# Quadcopter.net
KiCad netlist of a schematic drawn in Altium Designer
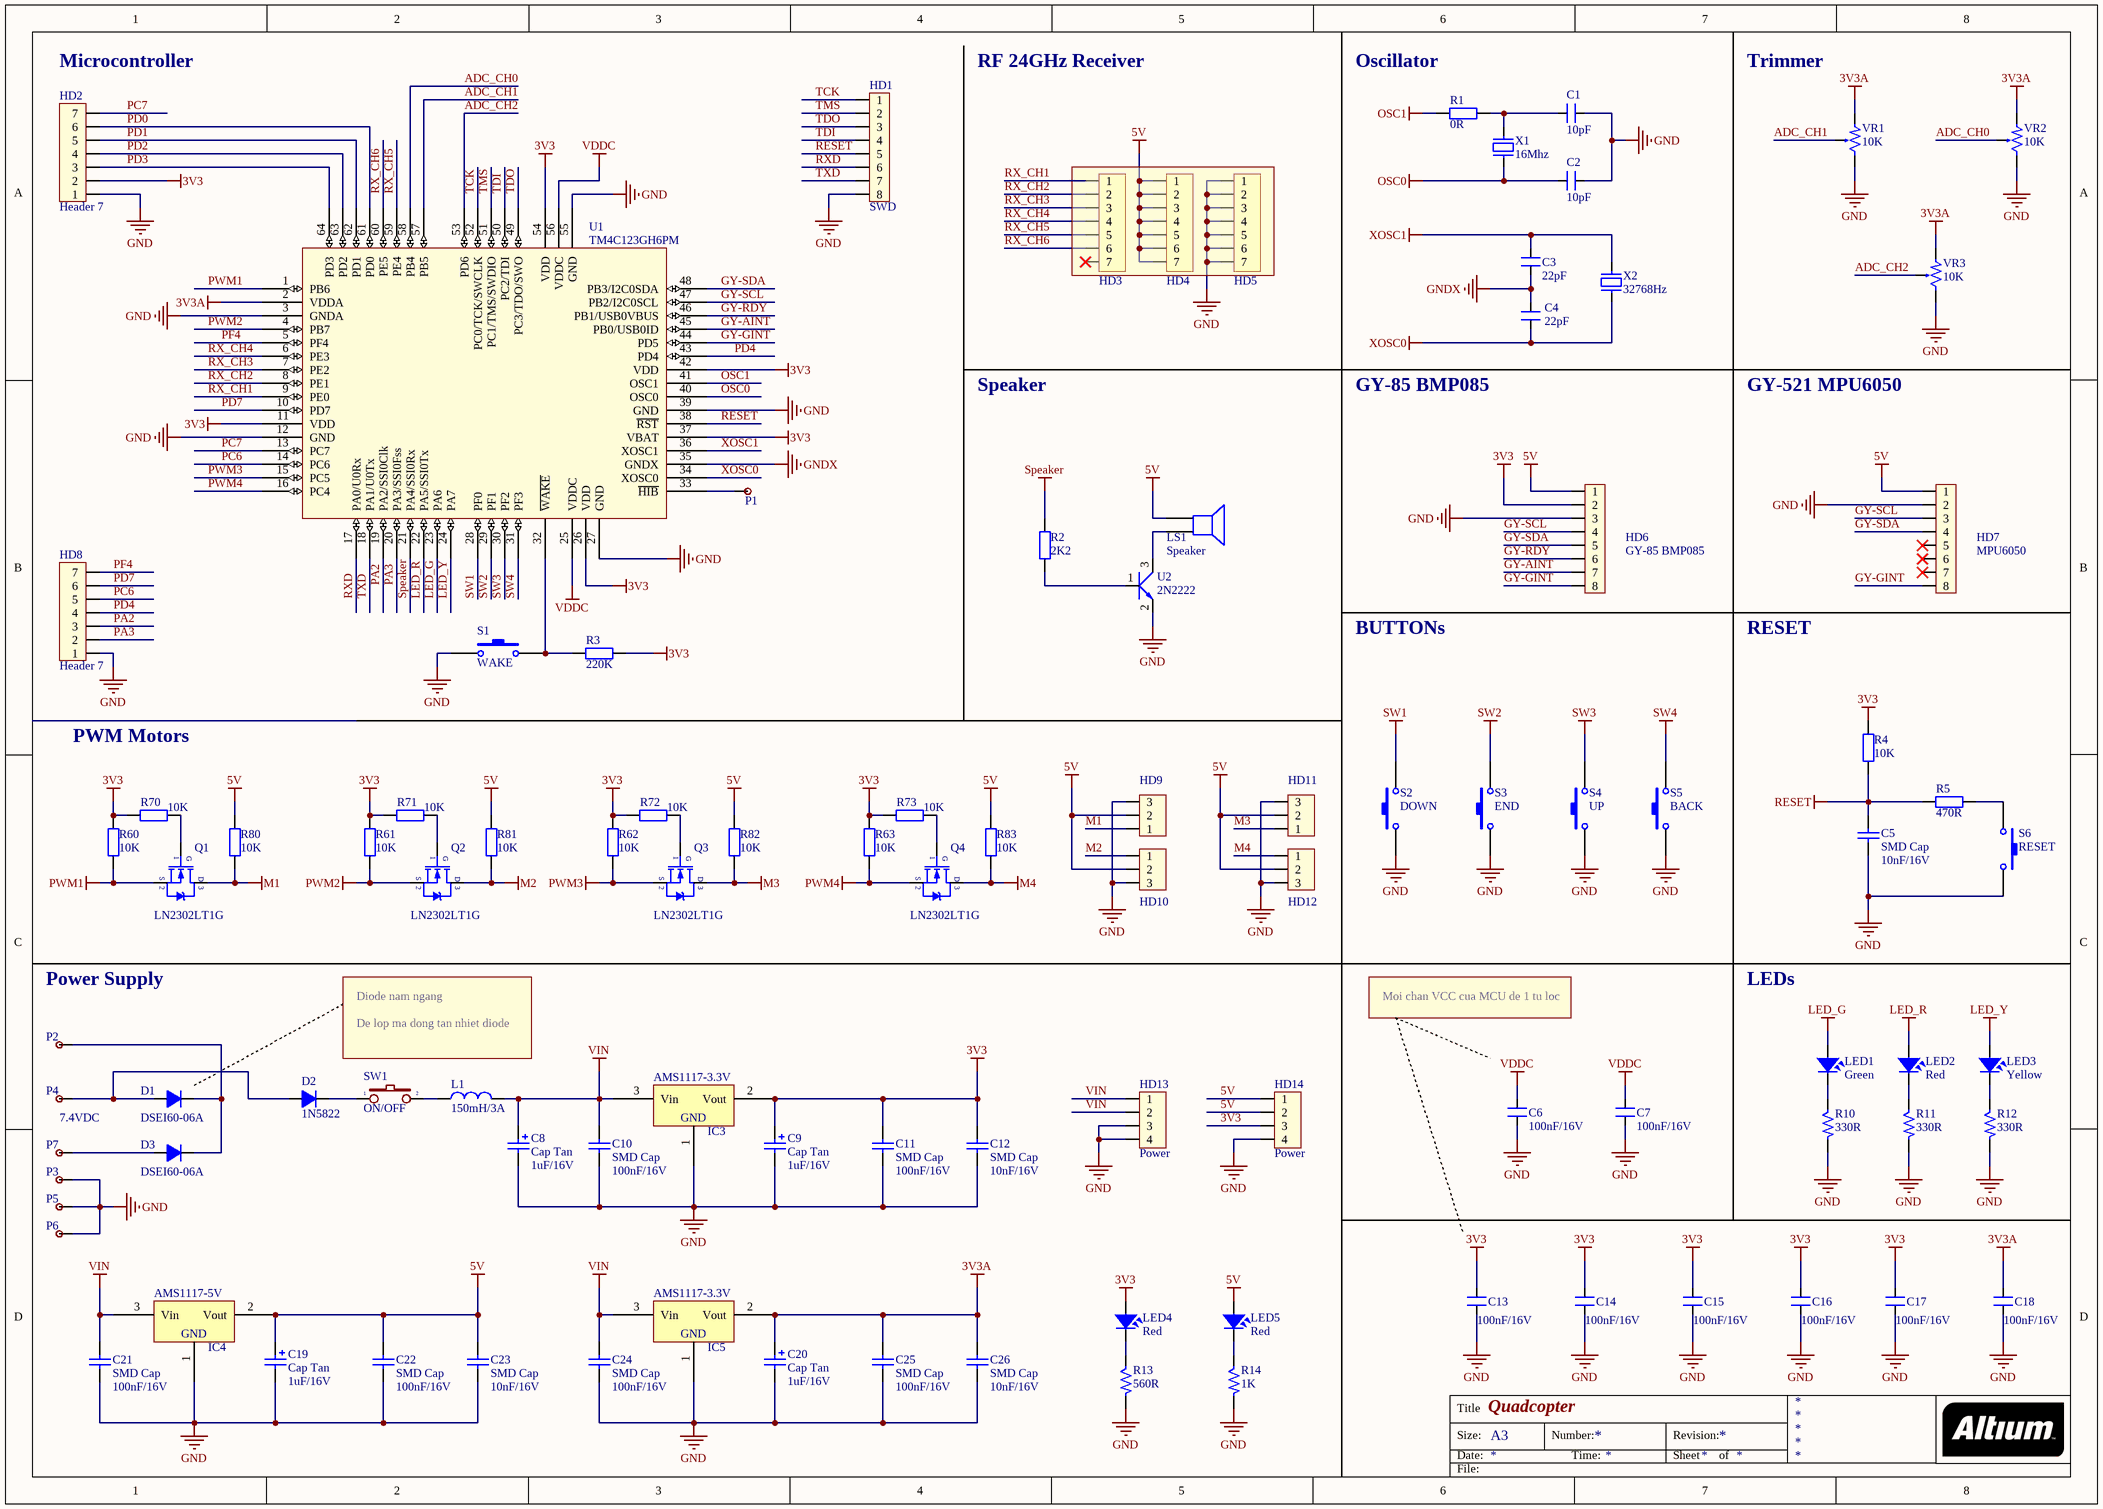
[diagram p0: Quadcopter.schdoc]

(export (version "E")
  (design (tool "Eeschema 10.0.6"))
  (components
    (comp (ref "C1")
      (value "10pF")
      (footprint "C0603")
      (description "0805-SMD Capacitor")
      (libsource (lib "syhaunguyen") (part "CN1"))
    )
    (comp (ref "C2")
      (value "10pF")
      (footprint "C0603")
      (description "0805-SMD Capacitor")
      (libsource (lib "syhaunguyen") (part "CN1"))
    )
    (comp (ref "C3")
      (value "22pF")
      (footprint "C0603")
      (description "0805-SMD Capacitor")
      (libsource (lib "syhaunguyen") (part "CN1"))
    )
    (comp (ref "C4")
      (value "22pF")
      (footprint "C0603")
      (description "0805-SMD Capacitor")
      (libsource (lib "syhaunguyen") (part "CN1"))
    )
    (comp (ref "C5")
      (value "SMD Cap")
      (footprint "C0603")
      (description "0805-10nF-50V Cap")
      (fields (field (name "ALTIUM_VALUE") "10nF/16V"))
      (libsource (lib "Miscellaneous Devices") (part "Cap"))
    )
    (comp (ref "C6")
      (value "100nF/16V")
      (footprint "C0603")
      (description "0805-SMD Capacitor")
      (fields (field (name "Comment") "SMD Cap"))
      (libsource (lib "syhaunguyen") (part "CN1"))
    )
    (comp (ref "C7")
      (value "100nF/16V")
      (footprint "C0603")
      (description "0805-SMD Capacitor")
      (fields (field (name "Comment") "SMD Cap"))
      (libsource (lib "syhaunguyen") (part "CN1"))
    )
    (comp (ref "C8")
      (value "Cap Tan")
      (footprint "CAP_TANTA_1uF_16V")
      (description "Cap Tantalum")
      (fields (field (name "ALTIUM_VALUE") "1uF/16V"))
      (libsource (lib "PassiveComponents_Sau") (part "Cap Pol2"))
    )
    (comp (ref "C9")
      (value "Cap Tan")
      (footprint "CAP_TANTA_1uF_16V")
      (description "Cap Tantalum")
      (fields (field (name "ALTIUM_VALUE") "1uF/16V"))
      (libsource (lib "PassiveComponents_Sau") (part "Cap Pol2"))
    )
    (comp (ref "C10")
      (value "SMD Cap")
      (footprint "C0603")
      (description "SMD Capacitor")
      (fields (field (name "ALTIUM_VALUE") "100nF/16V"))
      (libsource (lib "PassiveComponents_Sau") (part "Cap Cera"))
    )
    (comp (ref "C11")
      (value "SMD Cap")
      (footprint "C0603")
      (description "SMD Capacitor")
      (fields (field (name "ALTIUM_VALUE") "100nF/16V"))
      (libsource (lib "PassiveComponents_Sau") (part "Cap Cera"))
    )
    (comp (ref "C12")
      (value "SMD Cap")
      (footprint "C0603")
      (description "SMD Capacitor")
      (fields (field (name "ALTIUM_VALUE") "10nF/16V"))
      (libsource (lib "PassiveComponents_Sau") (part "Cap Cera"))
    )
    (comp (ref "C13")
      (value "100nF/16V")
      (footprint "C0603")
      (description "0805-SMD Capacitor")
      (fields (field (name "Comment") "SMD Cap"))
      (libsource (lib "syhaunguyen") (part "CN1"))
    )
    (comp (ref "C14")
      (value "100nF/16V")
      (footprint "C0603")
      (description "0805-SMD Capacitor")
      (fields (field (name "Comment") "SMD Cap"))
      (libsource (lib "syhaunguyen") (part "CN1"))
    )
    (comp (ref "C15")
      (value "100nF/16V")
      (footprint "C0603")
      (description "0805-SMD Capacitor")
      (fields (field (name "Comment") "SMD Cap"))
      (libsource (lib "syhaunguyen") (part "CN1"))
    )
    (comp (ref "C16")
      (value "100nF/16V")
      (footprint "C0603")
      (description "0805-SMD Capacitor")
      (fields (field (name "Comment") "SMD Cap"))
      (libsource (lib "syhaunguyen") (part "CN1"))
    )
    (comp (ref "C17")
      (value "100nF/16V")
      (footprint "C0603")
      (description "0805-SMD Capacitor")
      (fields (field (name "Comment") "SMD Cap"))
      (libsource (lib "syhaunguyen") (part "CN1"))
    )
    (comp (ref "C18")
      (value "100nF/16V")
      (footprint "C0603")
      (description "0805-SMD Capacitor")
      (fields (field (name "Comment") "SMD Cap"))
      (libsource (lib "syhaunguyen") (part "CN1"))
    )
    (comp (ref "C19")
      (value "Cap Tan")
      (footprint "CAP_TANTA_1uF_16V")
      (description "Cap Tantalum")
      (fields (field (name "ALTIUM_VALUE") "1uF/16V"))
      (libsource (lib "PassiveComponents_Sau") (part "Cap Pol2"))
    )
    (comp (ref "C20")
      (value "Cap Tan")
      (footprint "CAP_TANTA_1uF_16V")
      (description "Cap Tantalum")
      (fields (field (name "ALTIUM_VALUE") "1uF/16V"))
      (libsource (lib "PassiveComponents_Sau") (part "Cap Pol2"))
    )
    (comp (ref "C21")
      (value "SMD Cap")
      (footprint "C0603")
      (description "SMD Capacitor")
      (fields (field (name "ALTIUM_VALUE") "100nF/16V"))
      (libsource (lib "PassiveComponents_Sau") (part "Cap Cera"))
    )
    (comp (ref "C22")
      (value "SMD Cap")
      (footprint "C0603")
      (description "SMD Capacitor")
      (fields (field (name "ALTIUM_VALUE") "100nF/16V"))
      (libsource (lib "PassiveComponents_Sau") (part "Cap Cera"))
    )
    (comp (ref "C23")
      (value "SMD Cap")
      (footprint "C0603")
      (description "SMD Capacitor")
      (fields (field (name "ALTIUM_VALUE") "10nF/16V"))
      (libsource (lib "PassiveComponents_Sau") (part "Cap Cera"))
    )
    (comp (ref "C24")
      (value "SMD Cap")
      (footprint "C0603")
      (description "SMD Capacitor")
      (fields (field (name "ALTIUM_VALUE") "100nF/16V"))
      (libsource (lib "PassiveComponents_Sau") (part "Cap Cera"))
    )
    (comp (ref "C25")
      (value "SMD Cap")
      (footprint "C0603")
      (description "SMD Capacitor")
      (fields (field (name "ALTIUM_VALUE") "100nF/16V"))
      (libsource (lib "PassiveComponents_Sau") (part "Cap Cera"))
    )
    (comp (ref "C26")
      (value "SMD Cap")
      (footprint "C0603")
      (description "SMD Capacitor")
      (fields (field (name "ALTIUM_VALUE") "10nF/16V"))
      (libsource (lib "PassiveComponents_Sau") (part "Cap Cera"))
    )
    (comp (ref "D1")
      (value "DSEI60-06A")
      (footprint "DSEI60-06A_STAND")
      (description "Diode 60A")
      (libsource (lib "VNELEK") (part "D1A"))
    )
    (comp (ref "D2")
      (value "1N5822")
      (footprint "1N5822")
      (description "Diode  3A")
      (libsource (lib "VNELEK") (part "D1A"))
    )
    (comp (ref "D3")
      (value "DSEI60-06A")
      (footprint "DSEI60-06A_STAND")
      (description "Diode 60A")
      (libsource (lib "VNELEK") (part "D1A"))
    )
    (comp (ref "HD1")
      (value "SWD")
      (footprint "Header_8")
      (description "Hedear 8")
      (fields (field (name "CREAT BY") "VanDungEvn@Gmail.com"))
      (libsource (lib "VNELEK") (part "Hed8"))
    )
    (comp (ref "HD2") (value "Header 7") (footprint "Header_7") (libsource (lib "") (part "Hed7_1")))
    (comp (ref "HD3") (value "Header 7") (footprint "Header_7") (libsource (lib "Tran Tuan") (part "Hed7")))
    (comp (ref "HD4") (value "Header 7") (footprint "Header_7") (libsource (lib "Tran Tuan") (part "Hed7")))
    (comp (ref "HD5") (value "Header 7") (footprint "Header_7") (libsource (lib "Tran Tuan") (part "Hed7")))
    (comp (ref "HD6")
      (value "GY-85 BMP085")
      (footprint "Header_8")
      (description "Hedear 8")
      (fields (field (name "CREAT BY") "VanDungEvn@Gmail.com"))
      (libsource (lib "VNELEK") (part "Hed8"))
    )
    (comp (ref "HD7")
      (value "MPU6050")
      (footprint "Header_8")
      (description "Hedear 8")
      (fields (field (name "CREAT BY") "VanDungEvn@Gmail.com"))
      (libsource (lib "VNELEK") (part "Hed8"))
    )
    (comp (ref "HD8") (value "Header 7") (footprint "Header_7") (libsource (lib "") (part "Hed7_1")))
    (comp (ref "HD9")
      (value "Header 3")
      (footprint "JP3H_NAM")
      (description "Header 3 (Green)")
      (libsource (lib "") (part "Hed3_1"))
    )
    (comp (ref "HD10")
      (value "Header 3")
      (footprint "JP3H_NAM")
      (description "Header 3 (Green)")
      (libsource (lib "VNELEK") (part "Hed3"))
    )
    (comp (ref "HD11")
      (value "Header 3")
      (footprint "JP3H_NAM")
      (description "Header 3 (Green)")
      (libsource (lib "") (part "Hed3_1"))
    )
    (comp (ref "HD12")
      (value "Header 3")
      (footprint "JP3H_NAM")
      (description "Header 3 (Green)")
      (libsource (lib "VNELEK") (part "Hed3"))
    )
    (comp (ref "HD13")
      (value "Power")
      (footprint "Header_4")
      (description "Header 4 (Green)")
      (libsource (lib "VNELEK") (part "Hed4"))
    )
    (comp (ref "HD14")
      (value "Power")
      (footprint "Header_4")
      (description "Header 4 (Green)")
      (libsource (lib "VNELEK") (part "Hed4"))
    )
    (comp (ref "IC3")
      (value "AMS1117-3.3V")
      (footprint "AMS1117-5.0V")
      (libsource (lib "LuanVanPIR") (part "AMS1117"))
    )
    (comp (ref "IC4")
      (value "AMS1117-5V")
      (footprint "AMS1117-5.0V")
      (libsource (lib "LuanVanPIR") (part "AMS1117"))
    )
    (comp (ref "IC5")
      (value "AMS1117-3.3V")
      (footprint "AMS1117-5.0V")
      (libsource (lib "LuanVanPIR") (part "AMS1117"))
    )
    (comp (ref "L1")
      (value "150mH/3A")
      (footprint "Inductor 150mH,3A")
      (description "Inductor")
      (libsource (lib "VNELEK") (part "L1"))
    )
    (comp (ref "LED1")
      (value "Green")
      (footprint "Led 0805G")
      (description "LED Single colour Green and Red")
      (libsource (lib "VNELEK") (part "LED"))
    )
    (comp (ref "LED2")
      (value "Red")
      (footprint "Led 0805R")
      (description "LED Single colour Green and Red")
      (libsource (lib "VNELEK") (part "LED"))
    )
    (comp (ref "LED3")
      (value "Yellow")
      (footprint "Led 0805Y")
      (description "LED Single colour Green and Red")
      (libsource (lib "VNELEK") (part "LED"))
    )
    (comp (ref "LED4")
      (value "Red")
      (footprint "Led 0805R")
      (description "LED Single colour Green and Red")
      (libsource (lib "VNELEK") (part "LED"))
    )
    (comp (ref "LED5")
      (value "Red")
      (footprint "Led 0805R")
      (description "LED Single colour Green and Red")
      (libsource (lib "VNELEK") (part "LED"))
    )
    (comp (ref "LS1")
      (value "Speaker")
      (footprint "SPEAKER")
      (description "Loudspeaker")
      (fields (field (name "PUBLISHER") "Altium Limited"))
      (libsource (lib "Miscellaneous Devices") (part "Speaker"))
    )
    (comp (ref "P1") (value "Pad") (footprint "TP1") (libsource (lib "Tran Tuan") (part "Pad")))
    (comp (ref "P2") (value "Pad") (footprint "TP1") (libsource (lib "Tran Tuan") (part "Pad")))
    (comp (ref "P3") (value "Pad") (footprint "TP1") (libsource (lib "Tran Tuan") (part "Pad")))
    (comp (ref "P4") (value "Pad") (footprint "TP1") (libsource (lib "Tran Tuan") (part "Pad")))
    (comp (ref "P5") (value "Pad") (footprint "TP1") (libsource (lib "Tran Tuan") (part "Pad")))
    (comp (ref "P6") (value "Pad") (footprint "TP1") (libsource (lib "Tran Tuan") (part "Pad")))
    (comp (ref "P7") (value "Pad") (footprint "TP1") (libsource (lib "Tran Tuan") (part "Pad")))
    (comp (ref "Q1")
      (value "LN2302LT1G")
      (footprint "LN2302LT1G")
      (description "20V N-Channel Enhancement-Mode MOSFET")
      (libsource (lib "Tran Tuan") (part "LN2302LT1G"))
    )
    (comp (ref "Q2")
      (value "LN2302LT1G")
      (footprint "LN2302LT1G")
      (description "20V N-Channel Enhancement-Mode MOSFET")
      (libsource (lib "Tran Tuan") (part "LN2302LT1G"))
    )
    (comp (ref "Q3")
      (value "LN2302LT1G")
      (footprint "LN2302LT1G")
      (description "20V N-Channel Enhancement-Mode MOSFET")
      (libsource (lib "Tran Tuan") (part "LN2302LT1G"))
    )
    (comp (ref "Q4")
      (value "LN2302LT1G")
      (footprint "LN2302LT1G")
      (description "20V N-Channel Enhancement-Mode MOSFET")
      (libsource (lib "Tran Tuan") (part "LN2302LT1G"))
    )
    (comp (ref "R1")
      (value "0R")
      (footprint "RESC2012L")
      (description "Resistor")
      (fields (field (name "Comment") "Res2") (field (name "PUBLISHER") "Altium Limited"))
      (libsource (lib "") (part "Res2_2"))
    )
    (comp (ref "R2")
      (value "2K2")
      (footprint "RESC2012L")
      (description "Resistor")
      (fields (field (name "Comment") "Res2") (field (name "PUBLISHER") "Altium Limited"))
      (libsource (lib "") (part "Res2_3"))
    )
    (comp (ref "R3")
      (value "220K")
      (footprint "RESC2012L")
      (description "Resistor")
      (fields (field (name "Comment") "Res2") (field (name "PUBLISHER") "Altium Limited"))
      (libsource (lib "Miscellaneous Devices") (part "Res2"))
    )
    (comp (ref "R4")
      (value "10K")
      (footprint "RESC2012L")
      (description "Resistor")
      (fields (field (name "Comment") "Res2") (field (name "PUBLISHER") "Altium Limited"))
      (libsource (lib "") (part "Res2_1"))
    )
    (comp (ref "R5")
      (value "470R")
      (footprint "RESC2012L")
      (description "Resistor")
      (fields (field (name "Comment") "Res2") (field (name "PUBLISHER") "Altium Limited"))
      (libsource (lib "Miscellaneous Devices") (part "Res2"))
    )
    (comp (ref "R10")
      (value "330R")
      (footprint "RESC2012L")
      (description "Resistor 1/4W")
      (libsource (lib "VNELEK") (part "R"))
    )
    (comp (ref "R11")
      (value "330R")
      (footprint "RESC2012L")
      (description "Resistor 1/4W")
      (libsource (lib "VNELEK") (part "R"))
    )
    (comp (ref "R12")
      (value "330R")
      (footprint "RESC2012L")
      (description "Resistor 1/4W")
      (libsource (lib "VNELEK") (part "R"))
    )
    (comp (ref "R13")
      (value "560R")
      (footprint "RESC2012L")
      (description "Resistor 1/4W")
      (libsource (lib "VNELEK") (part "R"))
    )
    (comp (ref "R14")
      (value "1K")
      (footprint "RESC2012L")
      (description "Resistor 1/4W")
      (libsource (lib "VNELEK") (part "R"))
    )
    (comp (ref "R60")
      (value "10K")
      (footprint "RESC2012L")
      (description "Resistor")
      (fields (field (name "Comment") "Res2") (field (name "PUBLISHER") "Altium Limited"))
      (libsource (lib "") (part "Res2_1"))
    )
    (comp (ref "R61")
      (value "10K")
      (footprint "RESC2012L")
      (description "Resistor")
      (fields (field (name "Comment") "Res2") (field (name "PUBLISHER") "Altium Limited"))
      (libsource (lib "") (part "Res2_1"))
    )
    (comp (ref "R62")
      (value "10K")
      (footprint "RESC2012L")
      (description "Resistor")
      (fields (field (name "Comment") "Res2") (field (name "PUBLISHER") "Altium Limited"))
      (libsource (lib "") (part "Res2_1"))
    )
    (comp (ref "R63")
      (value "10K")
      (footprint "RESC2012L")
      (description "Resistor")
      (fields (field (name "Comment") "Res2") (field (name "PUBLISHER") "Altium Limited"))
      (libsource (lib "") (part "Res2_1"))
    )
    (comp (ref "R70")
      (value "10K")
      (footprint "RESC2012L")
      (description "Resistor")
      (fields (field (name "Comment") "Res2") (field (name "PUBLISHER") "Altium Limited"))
      (libsource (lib "Miscellaneous Devices") (part "Res2"))
    )
    (comp (ref "R71")
      (value "10K")
      (footprint "RESC2012L")
      (description "Resistor")
      (fields (field (name "Comment") "Res2") (field (name "PUBLISHER") "Altium Limited"))
      (libsource (lib "Miscellaneous Devices") (part "Res2"))
    )
    (comp (ref "R72")
      (value "10K")
      (footprint "RESC2012L")
      (description "Resistor")
      (fields (field (name "Comment") "Res2") (field (name "PUBLISHER") "Altium Limited"))
      (libsource (lib "Miscellaneous Devices") (part "Res2"))
    )
    (comp (ref "R73")
      (value "10K")
      (footprint "RESC2012L")
      (description "Resistor")
      (fields (field (name "Comment") "Res2") (field (name "PUBLISHER") "Altium Limited"))
      (libsource (lib "Miscellaneous Devices") (part "Res2"))
    )
    (comp (ref "R80")
      (value "10K")
      (footprint "RESC2012L")
      (description "Resistor")
      (fields (field (name "Comment") "Res2") (field (name "PUBLISHER") "Altium Limited"))
      (libsource (lib "") (part "Res2_1"))
    )
    (comp (ref "R81")
      (value "10K")
      (footprint "RESC2012L")
      (description "Resistor")
      (fields (field (name "Comment") "Res2") (field (name "PUBLISHER") "Altium Limited"))
      (libsource (lib "") (part "Res2_1"))
    )
    (comp (ref "R82")
      (value "10K")
      (footprint "RESC2012L")
      (description "Resistor")
      (fields (field (name "Comment") "Res2") (field (name "PUBLISHER") "Altium Limited"))
      (libsource (lib "") (part "Res2_1"))
    )
    (comp (ref "R83")
      (value "10K")
      (footprint "RESC2012L")
      (description "Resistor")
      (fields (field (name "Comment") "Res2") (field (name "PUBLISHER") "Altium Limited"))
      (libsource (lib "") (part "Res2_1"))
    )
    (comp (ref "S1")
      (value "WAKE")
      (footprint "BUTTON 2PIN TRON")
      (description "Switch")
      (fields (field (name "PUBLISHER") "Altium Limited"))
      (libsource (lib "Miscellaneous Devices") (part "SW-PB"))
    )
    (comp (ref "S2")
      (value "DOWN")
      (footprint "BUTTON 2PIN TRON")
      (description "Switch")
      (fields (field (name "PUBLISHER") "Altium Limited"))
      (libsource (lib "Miscellaneous Devices") (part "SW-PB"))
    )
    (comp (ref "S3")
      (value "END")
      (footprint "BUTTON 2PIN TRON")
      (description "Switch")
      (fields (field (name "PUBLISHER") "Altium Limited"))
      (libsource (lib "Miscellaneous Devices") (part "SW-PB"))
    )
    (comp (ref "S4")
      (value "UP")
      (footprint "BUTTON 2PIN TRON")
      (description "Switch")
      (fields (field (name "PUBLISHER") "Altium Limited"))
      (libsource (lib "Miscellaneous Devices") (part "SW-PB"))
    )
    (comp (ref "S5")
      (value "BACK")
      (footprint "BUTTON 2PIN TRON")
      (description "Switch")
      (fields (field (name "PUBLISHER") "Altium Limited"))
      (libsource (lib "Miscellaneous Devices") (part "SW-PB"))
    )
    (comp (ref "S6")
      (value "RESET")
      (footprint "BUTTON 2PIN TRON")
      (description "Switch")
      (fields (field (name "PUBLISHER") "Altium Limited"))
      (libsource (lib "Miscellaneous Devices") (part "SW-PB"))
    )
    (comp (ref "SW1")
      (value "ON/OFF")
      (footprint "CKCD11-101")
      (description "Switch button 2 pin")
      (libsource (lib "VNELEK") (part "SW2"))
    )
    (comp (ref "U1")
      (value "TM4C123GH6PM")
      (footprint "TM4C123GH6PM")
      (description "Tiva C Series Microcontroller")
      (libsource (lib "Tran Tuan") (part "TM4C123GH6PM"))
    )
    (comp (ref "U2")
      (value "2N2222")
      (footprint "MMBT2222A")
      (description "NPN switching transistors")
      (libsource (lib "Tran Tuan") (part "2N2222"))
    )
    (comp (ref "VR1")
      (value "10K")
      (footprint "VR")
      (description "Var Resistor")
      (libsource (lib "VNELEK") (part "VR1"))
    )
    (comp (ref "VR2")
      (value "10K")
      (footprint "VR")
      (description "Var Resistor")
      (libsource (lib "VNELEK") (part "VR1"))
    )
    (comp (ref "VR3")
      (value "10K")
      (footprint "VR")
      (description "Var Resistor")
      (libsource (lib "VNELEK") (part "VR1"))
    )
    (comp (ref "X1")
      (value "16Mhz")
      (footprint "CSTCE16M0V53-R0")
      (description "Crystal For all Crystal 2pin.")
      (libsource (lib "syhaunguyen") (part "XT2"))
    )
    (comp (ref "X2")
      (value "32768Hz")
      (footprint "32.678 Khz")
      (description "Crystal For all Crystal 2pin.")
      (libsource (lib "syhaunguyen") (part "XT2"))
    )
  )
  (nets
    (net (code "1") (name "/ADC_CH0") (class "Default")
      (node (ref "U1") (pin "58") (pinfunction "PB4_58") (pintype "bidirectional"))
      (node (ref "VR2") (pin "2") (pinfunction "2_2") (pintype "passive"))
    )
    (net (code "2") (name "/ADC_CH1") (class "Default")
      (node (ref "U1") (pin "57") (pinfunction "PB5_57") (pintype "bidirectional"))
      (node (ref "VR1") (pin "2") (pinfunction "2_2") (pintype "passive"))
    )
    (net (code "3") (name "/ADC_CH2") (class "Default")
      (node (ref "U1") (pin "53") (pinfunction "PD6_53") (pintype "bidirectional"))
      (node (ref "VR3") (pin "2") (pinfunction "2_2") (pintype "passive"))
    )
    (net (code "4") (name "/GY-AINT") (class "Default")
      (node (ref "HD6") (pin "7") (pinfunction "7_7") (pintype "passive"))
      (node (ref "U1") (pin "45") (pinfunction "PB0/USB0ID_45") (pintype "bidirectional"))
    )
    (net (code "5") (name "/GY-GINT") (class "Default")
      (node (ref "HD6") (pin "8") (pinfunction "8_8") (pintype "passive"))
      (node (ref "HD7") (pin "8") (pinfunction "8_8") (pintype "passive"))
      (node (ref "U1") (pin "44") (pinfunction "PD5_44") (pintype "bidirectional"))
    )
    (net (code "6") (name "/GY-RDY") (class "Default")
      (node (ref "HD6") (pin "6") (pinfunction "6_6") (pintype "passive"))
      (node (ref "U1") (pin "46") (pinfunction "PB1/USB0VBUS_46") (pintype "bidirectional"))
    )
    (net (code "7") (name "/GY-SCL") (class "Default")
      (node (ref "HD6") (pin "4") (pinfunction "4_4") (pintype "passive"))
      (node (ref "HD7") (pin "3") (pinfunction "3_3") (pintype "passive"))
      (node (ref "U1") (pin "47") (pinfunction "PB2/I2C0SCL_47") (pintype "bidirectional"))
    )
    (net (code "8") (name "/GY-SDA") (class "Default")
      (node (ref "HD6") (pin "5") (pinfunction "5_5") (pintype "passive"))
      (node (ref "HD7") (pin "4") (pinfunction "4_4") (pintype "passive"))
      (node (ref "U1") (pin "48") (pinfunction "PB3/I2C0SDA_48") (pintype "bidirectional"))
    )
    (net (code "9") (name "/PA2") (class "Default")
      (node (ref "HD8") (pin "3") (pinfunction "3_3") (pintype "passive"))
      (node (ref "U1") (pin "19") (pinfunction "PA2/SSI0Clk_19") (pintype "bidirectional"))
    )
    (net (code "10") (name "/PA3") (class "Default")
      (node (ref "HD8") (pin "2") (pinfunction "2_2") (pintype "passive"))
      (node (ref "U1") (pin "20") (pinfunction "PA3/SSI0Fss_20") (pintype "bidirectional"))
    )
    (net (code "11") (name "/PC6") (class "Default")
      (node (ref "HD8") (pin "5") (pinfunction "5_5") (pintype "passive"))
      (node (ref "U1") (pin "14") (pinfunction "PC6_14") (pintype "bidirectional"))
    )
    (net (code "12") (name "/PC7") (class "Default")
      (node (ref "HD2") (pin "7") (pinfunction "7_7") (pintype "passive"))
      (node (ref "U1") (pin "13") (pinfunction "PC7_13") (pintype "bidirectional"))
    )
    (net (code "13") (name "/PD0") (class "Default")
      (node (ref "HD2") (pin "6") (pinfunction "6_6") (pintype "passive"))
      (node (ref "U1") (pin "61") (pinfunction "PD0_61") (pintype "bidirectional"))
    )
    (net (code "14") (name "/PD1") (class "Default")
      (node (ref "HD2") (pin "5") (pinfunction "5_5") (pintype "passive"))
      (node (ref "U1") (pin "62") (pinfunction "PD1_62") (pintype "bidirectional"))
    )
    (net (code "15") (name "/PD2") (class "Default")
      (node (ref "HD2") (pin "4") (pinfunction "4_4") (pintype "passive"))
      (node (ref "U1") (pin "63") (pinfunction "PD2_63") (pintype "bidirectional"))
    )
    (net (code "16") (name "/PD3") (class "Default")
      (node (ref "HD2") (pin "3") (pinfunction "3_3") (pintype "passive"))
      (node (ref "U1") (pin "64") (pinfunction "PD3_64") (pintype "bidirectional"))
    )
    (net (code "17") (name "/PD4") (class "Default")
      (node (ref "HD8") (pin "4") (pinfunction "4_4") (pintype "passive"))
      (node (ref "U1") (pin "43") (pinfunction "PD4_43") (pintype "bidirectional"))
    )
    (net (code "18") (name "/PD7") (class "Default")
      (node (ref "HD8") (pin "6") (pinfunction "6_6") (pintype "passive"))
      (node (ref "U1") (pin "10") (pinfunction "PD7_10") (pintype "bidirectional"))
    )
    (net (code "19") (name "/PF4") (class "Default")
      (node (ref "HD8") (pin "7") (pinfunction "7_7") (pintype "passive"))
      (node (ref "U1") (pin "5") (pinfunction "PF4_5") (pintype "bidirectional"))
    )
    (net (code "20") (name "/RXD") (class "Default")
      (node (ref "HD1") (pin "6") (pinfunction "6_6") (pintype "passive"))
      (node (ref "U1") (pin "17") (pinfunction "PA0/U0Rx_17") (pintype "bidirectional"))
    )
    (net (code "21") (name "/RX_CH1") (class "Default")
      (node (ref "HD3") (pin "1") (pinfunction "1_1") (pintype "passive"))
      (node (ref "U1") (pin "9") (pinfunction "PE0_9") (pintype "bidirectional"))
    )
    (net (code "22") (name "/RX_CH2") (class "Default")
      (node (ref "HD3") (pin "2") (pinfunction "2_2") (pintype "passive"))
      (node (ref "U1") (pin "8") (pinfunction "PE1_8") (pintype "bidirectional"))
    )
    (net (code "23") (name "/RX_CH3") (class "Default")
      (node (ref "HD3") (pin "3") (pinfunction "3_3") (pintype "passive"))
      (node (ref "U1") (pin "7") (pinfunction "PE2_7") (pintype "bidirectional"))
    )
    (net (code "24") (name "/RX_CH4") (class "Default")
      (node (ref "HD3") (pin "4") (pinfunction "4_4") (pintype "passive"))
      (node (ref "U1") (pin "6") (pinfunction "PE3_6") (pintype "bidirectional"))
    )
    (net (code "25") (name "/RX_CH5") (class "Default")
      (node (ref "HD3") (pin "5") (pinfunction "5_5") (pintype "passive"))
      (node (ref "U1") (pin "59") (pinfunction "PE4_59") (pintype "bidirectional"))
    )
    (net (code "26") (name "/RX_CH6") (class "Default")
      (node (ref "HD3") (pin "6") (pinfunction "6_6") (pintype "passive"))
      (node (ref "U1") (pin "60") (pinfunction "PE5_60") (pintype "bidirectional"))
    )
    (net (code "27") (name "/TCK") (class "Default")
      (node (ref "HD1") (pin "1") (pinfunction "1_1") (pintype "passive"))
      (node (ref "U1") (pin "52") (pinfunction "PC0/TCK/SWCLK_52") (pintype "bidirectional"))
    )
    (net (code "28") (name "/TDI") (class "Default")
      (node (ref "HD1") (pin "4") (pinfunction "4_4") (pintype "passive"))
      (node (ref "U1") (pin "50") (pinfunction "PC2/TDI_50") (pintype "bidirectional"))
    )
    (net (code "29") (name "/TDO") (class "Default")
      (node (ref "HD1") (pin "3") (pinfunction "3_3") (pintype "passive"))
      (node (ref "U1") (pin "49") (pinfunction "PC3/TDO/SWO_49") (pintype "bidirectional"))
    )
    (net (code "30") (name "/TMS") (class "Default")
      (node (ref "HD1") (pin "2") (pinfunction "2_2") (pintype "passive"))
      (node (ref "U1") (pin "51") (pinfunction "PC1/TMS/SWDIO_51") (pintype "bidirectional"))
    )
    (net (code "31") (name "/TXD") (class "Default")
      (node (ref "HD1") (pin "7") (pinfunction "7_7") (pintype "passive"))
      (node (ref "U1") (pin "18") (pinfunction "PA1/U0Tx_18") (pintype "bidirectional"))
    )
    (net (code "32") (name "3V3") (class "Default")
      (node (ref "C11") (pin "2") (pinfunction "2_2") (pintype "passive"))
      (node (ref "C12") (pin "2") (pinfunction "2_2") (pintype "passive"))
      (node (ref "C13") (pin "1") (pinfunction "1_1") (pintype "passive"))
      (node (ref "C14") (pin "1") (pinfunction "1_1") (pintype "passive"))
      (node (ref "C15") (pin "1") (pinfunction "1_1") (pintype "passive"))
      (node (ref "C16") (pin "1") (pinfunction "1_1") (pintype "passive"))
      (node (ref "C17") (pin "1") (pinfunction "1_1") (pintype "passive"))
      (node (ref "C9") (pin "1") (pinfunction "+_1") (pintype "passive"))
      (node (ref "HD14") (pin "3") (pinfunction "3_3") (pintype "passive"))
      (node (ref "HD2") (pin "2") (pinfunction "2_2") (pintype "passive"))
      (node (ref "HD6") (pin "2") (pinfunction "2_2") (pintype "passive"))
      (node (ref "IC3") (pin "2") (pinfunction "Vout_2") (pintype "passive"))
      (node (ref "LED4") (pin "1") (pinfunction "1_1") (pintype "passive"))
      (node (ref "R3") (pin "1") (pinfunction "1_1") (pintype "passive"))
      (node (ref "R4") (pin "2") (pinfunction "2_2") (pintype "passive"))
      (node (ref "R60") (pin "2") (pinfunction "2_2") (pintype "passive"))
      (node (ref "R61") (pin "2") (pinfunction "2_2") (pintype "passive"))
      (node (ref "R62") (pin "2") (pinfunction "2_2") (pintype "passive"))
      (node (ref "R63") (pin "2") (pinfunction "2_2") (pintype "passive"))
      (node (ref "R70") (pin "2") (pinfunction "2_2") (pintype "passive"))
      (node (ref "R71") (pin "2") (pinfunction "2_2") (pintype "passive"))
      (node (ref "R72") (pin "2") (pinfunction "2_2") (pintype "passive"))
      (node (ref "R73") (pin "2") (pinfunction "2_2") (pintype "passive"))
      (node (ref "U1") (pin "11") (pinfunction "VDD_11") (pintype "power_in"))
      (node (ref "U1") (pin "26") (pinfunction "VDD_26") (pintype "power_in"))
      (node (ref "U1") (pin "37") (pinfunction "VBAT_37") (pintype "power_in"))
      (node (ref "U1") (pin "42") (pinfunction "VDD_42") (pintype "power_in"))
      (node (ref "U1") (pin "54") (pinfunction "VDD_54") (pintype "power_in"))
    )
    (net (code "33") (name "3V3A") (class "Default")
      (node (ref "C18") (pin "1") (pinfunction "1_1") (pintype "passive"))
      (node (ref "C20") (pin "1") (pinfunction "+_1") (pintype "passive"))
      (node (ref "C25") (pin "2") (pinfunction "2_2") (pintype "passive"))
      (node (ref "C26") (pin "2") (pinfunction "2_2") (pintype "passive"))
      (node (ref "IC5") (pin "2") (pinfunction "Vout_2") (pintype "passive"))
      (node (ref "U1") (pin "2") (pinfunction "VDDA_2") (pintype "power_in"))
      (node (ref "VR1") (pin "1") (pinfunction "1_1") (pintype "passive"))
      (node (ref "VR2") (pin "1") (pinfunction "1_1") (pintype "passive"))
      (node (ref "VR3") (pin "1") (pinfunction "1_1") (pintype "passive"))
    )
    (net (code "34") (name "5V") (class "Default")
      (node (ref "C19") (pin "1") (pinfunction "+_1") (pintype "passive"))
      (node (ref "C22") (pin "2") (pinfunction "2_2") (pintype "passive"))
      (node (ref "C23") (pin "2") (pinfunction "2_2") (pintype "passive"))
      (node (ref "HD10") (pin "2") (pinfunction "2_2") (pintype "passive"))
      (node (ref "HD11") (pin "2") (pinfunction "2_2") (pintype "passive"))
      (node (ref "HD12") (pin "2") (pinfunction "2_2") (pintype "passive"))
      (node (ref "HD14") (pin "1") (pinfunction "1_1") (pintype "passive"))
      (node (ref "HD14") (pin "2") (pinfunction "2_2") (pintype "passive"))
      (node (ref "HD4") (pin "1") (pinfunction "1_1") (pintype "passive"))
      (node (ref "HD4") (pin "2") (pinfunction "2_2") (pintype "passive"))
      (node (ref "HD4") (pin "3") (pinfunction "3_3") (pintype "passive"))
      (node (ref "HD4") (pin "4") (pinfunction "4_4") (pintype "passive"))
      (node (ref "HD4") (pin "5") (pinfunction "5_5") (pintype "passive"))
      (node (ref "HD4") (pin "6") (pinfunction "6_6") (pintype "passive"))
      (node (ref "HD4") (pin "7") (pinfunction "7_7") (pintype "passive"))
      (node (ref "HD6") (pin "1") (pinfunction "1_1") (pintype "passive"))
      (node (ref "HD7") (pin "1") (pinfunction "1_1") (pintype "passive"))
      (node (ref "HD9") (pin "2") (pinfunction "2_2") (pintype "passive"))
      (node (ref "IC4") (pin "2") (pinfunction "Vout_2") (pintype "passive"))
      (node (ref "LED5") (pin "1") (pinfunction "1_1") (pintype "passive"))
      (node (ref "LS1") (pin "2") (pinfunction "2_2") (pintype "passive"))
      (node (ref "R80") (pin "2") (pinfunction "2_2") (pintype "passive"))
      (node (ref "R81") (pin "2") (pinfunction "2_2") (pintype "passive"))
      (node (ref "R82") (pin "2") (pinfunction "2_2") (pintype "passive"))
      (node (ref "R83") (pin "2") (pinfunction "2_2") (pintype "passive"))
    )
    (net (code "35") (name "GND") (class "Default")
      (node (ref "C1") (pin "1") (pinfunction "1_1") (pintype "passive"))
      (node (ref "C10") (pin "1") (pinfunction "1_1") (pintype "passive"))
      (node (ref "C11") (pin "1") (pinfunction "1_1") (pintype "passive"))
      (node (ref "C12") (pin "1") (pinfunction "1_1") (pintype "passive"))
      (node (ref "C13") (pin "2") (pinfunction "2_2") (pintype "passive"))
      (node (ref "C14") (pin "2") (pinfunction "2_2") (pintype "passive"))
      (node (ref "C15") (pin "2") (pinfunction "2_2") (pintype "passive"))
      (node (ref "C16") (pin "2") (pinfunction "2_2") (pintype "passive"))
      (node (ref "C17") (pin "2") (pinfunction "2_2") (pintype "passive"))
      (node (ref "C18") (pin "2") (pinfunction "2_2") (pintype "passive"))
      (node (ref "C19") (pin "2") (pinfunction "-_2") (pintype "passive"))
      (node (ref "C2") (pin "1") (pinfunction "1_1") (pintype "passive"))
      (node (ref "C20") (pin "2") (pinfunction "-_2") (pintype "passive"))
      (node (ref "C21") (pin "1") (pinfunction "1_1") (pintype "passive"))
      (node (ref "C22") (pin "1") (pinfunction "1_1") (pintype "passive"))
      (node (ref "C23") (pin "1") (pinfunction "1_1") (pintype "passive"))
      (node (ref "C24") (pin "1") (pinfunction "1_1") (pintype "passive"))
      (node (ref "C25") (pin "1") (pinfunction "1_1") (pintype "passive"))
      (node (ref "C26") (pin "1") (pinfunction "1_1") (pintype "passive"))
      (node (ref "C5") (pin "2") (pinfunction "2_2") (pintype "passive"))
      (node (ref "C6") (pin "2") (pinfunction "2_2") (pintype "passive"))
      (node (ref "C7") (pin "2") (pinfunction "2_2") (pintype "passive"))
      (node (ref "C8") (pin "2") (pinfunction "-_2") (pintype "passive"))
      (node (ref "C9") (pin "2") (pinfunction "-_2") (pintype "passive"))
      (node (ref "HD1") (pin "8") (pinfunction "8_8") (pintype "passive"))
      (node (ref "HD10") (pin "3") (pinfunction "3_3") (pintype "passive"))
      (node (ref "HD11") (pin "3") (pinfunction "3_3") (pintype "passive"))
      (node (ref "HD12") (pin "3") (pinfunction "3_3") (pintype "passive"))
      (node (ref "HD13") (pin "3") (pinfunction "3_3") (pintype "passive"))
      (node (ref "HD13") (pin "4") (pinfunction "4_4") (pintype "passive"))
      (node (ref "HD14") (pin "4") (pinfunction "4_4") (pintype "passive"))
      (node (ref "HD2") (pin "1") (pinfunction "1_1") (pintype "passive"))
      (node (ref "HD5") (pin "1") (pinfunction "1_1") (pintype "passive"))
      (node (ref "HD5") (pin "2") (pinfunction "2_2") (pintype "passive"))
      (node (ref "HD5") (pin "3") (pinfunction "3_3") (pintype "passive"))
      (node (ref "HD5") (pin "4") (pinfunction "4_4") (pintype "passive"))
      (node (ref "HD5") (pin "5") (pinfunction "5_5") (pintype "passive"))
      (node (ref "HD5") (pin "6") (pinfunction "6_6") (pintype "passive"))
      (node (ref "HD5") (pin "7") (pinfunction "7_7") (pintype "passive"))
      (node (ref "HD6") (pin "3") (pinfunction "3_3") (pintype "passive"))
      (node (ref "HD7") (pin "2") (pinfunction "2_2") (pintype "passive"))
      (node (ref "HD8") (pin "1") (pinfunction "1_1") (pintype "passive"))
      (node (ref "HD9") (pin "3") (pinfunction "3_3") (pintype "passive"))
      (node (ref "IC3") (pin "1") (pinfunction "GND_1") (pintype "passive"))
      (node (ref "IC4") (pin "1") (pinfunction "GND_1") (pintype "passive"))
      (node (ref "IC5") (pin "1") (pinfunction "GND_1") (pintype "passive"))
      (node (ref "P3") (pin "1") (pinfunction "1_1") (pintype "passive"))
      (node (ref "P5") (pin "1") (pinfunction "1_1") (pintype "passive"))
      (node (ref "P6") (pin "1") (pinfunction "1_1") (pintype "passive"))
      (node (ref "R10") (pin "2") (pinfunction "2_2") (pintype "passive"))
      (node (ref "R11") (pin "2") (pinfunction "2_2") (pintype "passive"))
      (node (ref "R12") (pin "2") (pinfunction "2_2") (pintype "passive"))
      (node (ref "R13") (pin "2") (pinfunction "2_2") (pintype "passive"))
      (node (ref "R14") (pin "2") (pinfunction "2_2") (pintype "passive"))
      (node (ref "S1") (pin "1") (pinfunction "1_1") (pintype "passive"))
      (node (ref "S2") (pin "1") (pinfunction "1_1") (pintype "passive"))
      (node (ref "S3") (pin "1") (pinfunction "1_1") (pintype "passive"))
      (node (ref "S4") (pin "1") (pinfunction "1_1") (pintype "passive"))
      (node (ref "S5") (pin "1") (pinfunction "1_1") (pintype "passive"))
      (node (ref "S6") (pin "2") (pinfunction "2_2") (pintype "passive"))
      (node (ref "U1") (pin "12") (pinfunction "GND_12") (pintype "power_in"))
      (node (ref "U1") (pin "27") (pinfunction "GND_27") (pintype "power_in"))
      (node (ref "U1") (pin "3") (pinfunction "GNDA_3") (pintype "power_in"))
      (node (ref "U1") (pin "39") (pinfunction "GND_39") (pintype "power_in"))
      (node (ref "U1") (pin "55") (pinfunction "GND_55") (pintype "power_in"))
      (node (ref "U2") (pin "2") (pinfunction "E_2") (pintype "passive"))
      (node (ref "VR1") (pin "3") (pinfunction "3_3") (pintype "passive"))
      (node (ref "VR2") (pin "3") (pinfunction "3_3") (pintype "passive"))
      (node (ref "VR3") (pin "3") (pinfunction "3_3") (pintype "passive"))
    )
    (net (code "36") (name "GNDX") (class "Default")
      (node (ref "C3") (pin "2") (pinfunction "2_2") (pintype "passive"))
      (node (ref "C4") (pin "1") (pinfunction "1_1") (pintype "passive"))
      (node (ref "U1") (pin "35") (pinfunction "GNDX_35") (pintype "power_in"))
    )
    (net (code "37") (name "LED_G") (class "Default")
      (node (ref "LED1") (pin "1") (pinfunction "1_1") (pintype "passive"))
      (node (ref "U1") (pin "23") (pinfunction "PA6_23") (pintype "bidirectional"))
    )
    (net (code "38") (name "LED_R") (class "Default")
      (node (ref "LED2") (pin "1") (pinfunction "1_1") (pintype "passive"))
      (node (ref "U1") (pin "22") (pinfunction "PA5/SSI0Tx_22") (pintype "bidirectional"))
    )
    (net (code "39") (name "LED_Y") (class "Default")
      (node (ref "LED3") (pin "1") (pinfunction "1_1") (pintype "passive"))
      (node (ref "U1") (pin "24") (pinfunction "PA7_24") (pintype "bidirectional"))
    )
    (net (code "40") (name "M1") (class "Default")
      (node (ref "HD9") (pin "1") (pinfunction "1_1") (pintype "passive"))
      (node (ref "Q1") (pin "3") (pinfunction "D_3") (pintype "passive"))
      (node (ref "R80") (pin "1") (pinfunction "1_1") (pintype "passive"))
    )
    (net (code "41") (name "M2") (class "Default")
      (node (ref "HD10") (pin "1") (pinfunction "1_1") (pintype "passive"))
      (node (ref "Q2") (pin "3") (pinfunction "D_3") (pintype "passive"))
      (node (ref "R81") (pin "1") (pinfunction "1_1") (pintype "passive"))
    )
    (net (code "42") (name "M3") (class "Default")
      (node (ref "HD11") (pin "1") (pinfunction "1_1") (pintype "passive"))
      (node (ref "Q3") (pin "3") (pinfunction "D_3") (pintype "passive"))
      (node (ref "R82") (pin "1") (pinfunction "1_1") (pintype "passive"))
    )
    (net (code "43") (name "M4") (class "Default")
      (node (ref "HD12") (pin "1") (pinfunction "1_1") (pintype "passive"))
      (node (ref "Q4") (pin "3") (pinfunction "D_3") (pintype "passive"))
      (node (ref "R83") (pin "1") (pinfunction "1_1") (pintype "passive"))
    )
    (net (code "44") (name "Net-(C1-Pad2)") (class "Default")
      (node (ref "C1") (pin "2") (pinfunction "2_2") (pintype "passive"))
      (node (ref "R1") (pin "2") (pinfunction "2_2") (pintype "passive"))
      (node (ref "X1") (pin "1") (pinfunction "1_1") (pintype "passive"))
    )
    (net (code "45") (name "Net-(D1-A)") (class "Default")
      (node (ref "D1") (pin "2") (pinfunction "A_2") (pintype "passive"))
      (node (ref "D3") (pin "2") (pinfunction "A_2") (pintype "passive"))
      (node (ref "P2") (pin "1") (pinfunction "1_1") (pintype "passive"))
    )
    (net (code "46") (name "Net-(D1-K)") (class "Default")
      (node (ref "D1") (pin "1") (pinfunction "K_1") (pintype "passive"))
      (node (ref "D2") (pin "1") (pinfunction "K_1") (pintype "passive"))
      (node (ref "P4") (pin "1") (pinfunction "1_1") (pintype "passive"))
    )
    (net (code "47") (name "Net-(D2-A)") (class "Default")
      (node (ref "D2") (pin "2") (pinfunction "A_2") (pintype "passive"))
      (node (ref "SW1") (pin "1") (pinfunction "1_1") (pintype "passive"))
    )
    (net (code "48") (name "Net-(D3-K)") (class "Default")
      (node (ref "D3") (pin "1") (pinfunction "K_1") (pintype "passive"))
      (node (ref "P7") (pin "1") (pinfunction "1_1") (pintype "passive"))
    )
    (net (code "49") (name "Net-(L1-Pad1)") (class "Default")
      (node (ref "L1") (pin "1") (pinfunction "1_1") (pintype "passive"))
      (node (ref "SW1") (pin "2") (pinfunction "2_2") (pintype "passive"))
    )
    (net (code "50") (name "Net-(LED1-Pad2)") (class "Default")
      (node (ref "LED1") (pin "2") (pinfunction "2_2") (pintype "passive"))
      (node (ref "R10") (pin "1") (pinfunction "1_1") (pintype "passive"))
    )
    (net (code "51") (name "Net-(LED2-Pad2)") (class "Default")
      (node (ref "LED2") (pin "2") (pinfunction "2_2") (pintype "passive"))
      (node (ref "R11") (pin "1") (pinfunction "1_1") (pintype "passive"))
    )
    (net (code "52") (name "Net-(LED3-Pad2)") (class "Default")
      (node (ref "LED3") (pin "2") (pinfunction "2_2") (pintype "passive"))
      (node (ref "R12") (pin "1") (pinfunction "1_1") (pintype "passive"))
    )
    (net (code "53") (name "Net-(LED4-Pad2)") (class "Default")
      (node (ref "LED4") (pin "2") (pinfunction "2_2") (pintype "passive"))
      (node (ref "R13") (pin "1") (pinfunction "1_1") (pintype "passive"))
    )
    (net (code "54") (name "Net-(LED5-Pad2)") (class "Default")
      (node (ref "LED5") (pin "2") (pinfunction "2_2") (pintype "passive"))
      (node (ref "R14") (pin "1") (pinfunction "1_1") (pintype "passive"))
    )
    (net (code "55") (name "Net-(Q1-G)") (class "Default")
      (node (ref "Q1") (pin "1") (pinfunction "G_1") (pintype "passive"))
      (node (ref "R70") (pin "1") (pinfunction "1_1") (pintype "passive"))
    )
    (net (code "56") (name "Net-(Q2-G)") (class "Default")
      (node (ref "Q2") (pin "1") (pinfunction "G_1") (pintype "passive"))
      (node (ref "R71") (pin "1") (pinfunction "1_1") (pintype "passive"))
    )
    (net (code "57") (name "Net-(Q3-G)") (class "Default")
      (node (ref "Q3") (pin "1") (pinfunction "G_1") (pintype "passive"))
      (node (ref "R72") (pin "1") (pinfunction "1_1") (pintype "passive"))
    )
    (net (code "58") (name "Net-(Q4-G)") (class "Default")
      (node (ref "Q4") (pin "1") (pinfunction "G_1") (pintype "passive"))
      (node (ref "R73") (pin "1") (pinfunction "1_1") (pintype "passive"))
    )
    (net (code "59") (name "Net-(R5-Pad1)") (class "Default")
      (node (ref "R5") (pin "1") (pinfunction "1_1") (pintype "passive"))
      (node (ref "S6") (pin "1") (pinfunction "1_1") (pintype "passive"))
    )
    (net (code "60") (name "Net-(U1-~{HIB})") (class "Default")
      (node (ref "P1") (pin "1") (pinfunction "1_1") (pintype "passive"))
      (node (ref "U1") (pin "33") (pinfunction "~{HIB}_33") (pintype "passive"))
    )
    (net (code "61") (name "Net-(U1-~{WAKE})") (class "Default")
      (node (ref "R3") (pin "2") (pinfunction "2_2") (pintype "passive"))
      (node (ref "S1") (pin "2") (pinfunction "2_2") (pintype "passive"))
      (node (ref "U1") (pin "32") (pinfunction "~{WAKE}_32") (pintype "passive"))
    )
    (net (code "62") (name "Net-(U2-B)") (class "Default")
      (node (ref "R2") (pin "2") (pinfunction "2_2") (pintype "passive"))
      (node (ref "U2") (pin "1") (pinfunction "B_1") (pintype "passive"))
    )
    (net (code "63") (name "Net-(U2-C)") (class "Default")
      (node (ref "LS1") (pin "1") (pinfunction "1_1") (pintype "passive"))
      (node (ref "U2") (pin "3") (pinfunction "C_3") (pintype "passive"))
    )
    (net (code "64") (name "OSC0") (class "Default")
      (node (ref "C2") (pin "2") (pinfunction "2_2") (pintype "passive"))
      (node (ref "U1") (pin "40") (pinfunction "OSC0_40") (pintype "passive"))
      (node (ref "X1") (pin "2") (pinfunction "2_2") (pintype "passive"))
    )
    (net (code "65") (name "OSC1") (class "Default")
      (node (ref "R1") (pin "1") (pinfunction "1_1") (pintype "passive"))
      (node (ref "U1") (pin "41") (pinfunction "OSC1_41") (pintype "passive"))
    )
    (net (code "66") (name "PWM1") (class "Default")
      (node (ref "Q1") (pin "2") (pinfunction "S_2") (pintype "passive"))
      (node (ref "R60") (pin "1") (pinfunction "1_1") (pintype "passive"))
      (node (ref "U1") (pin "1") (pinfunction "PB6_1") (pintype "bidirectional"))
    )
    (net (code "67") (name "PWM2") (class "Default")
      (node (ref "Q2") (pin "2") (pinfunction "S_2") (pintype "passive"))
      (node (ref "R61") (pin "1") (pinfunction "1_1") (pintype "passive"))
      (node (ref "U1") (pin "4") (pinfunction "PB7_4") (pintype "bidirectional"))
    )
    (net (code "68") (name "PWM3") (class "Default")
      (node (ref "Q3") (pin "2") (pinfunction "S_2") (pintype "passive"))
      (node (ref "R62") (pin "1") (pinfunction "1_1") (pintype "passive"))
      (node (ref "U1") (pin "15") (pinfunction "PC5_15") (pintype "bidirectional"))
    )
    (net (code "69") (name "PWM4") (class "Default")
      (node (ref "Q4") (pin "2") (pinfunction "S_2") (pintype "passive"))
      (node (ref "R63") (pin "1") (pinfunction "1_1") (pintype "passive"))
      (node (ref "U1") (pin "16") (pinfunction "PC4_16") (pintype "bidirectional"))
    )
    (net (code "70") (name "RESET") (class "Default")
      (node (ref "C5") (pin "1") (pinfunction "1_1") (pintype "passive"))
      (node (ref "HD1") (pin "5") (pinfunction "5_5") (pintype "passive"))
      (node (ref "R4") (pin "1") (pinfunction "1_1") (pintype "passive"))
      (node (ref "R5") (pin "2") (pinfunction "2_2") (pintype "passive"))
      (node (ref "U1") (pin "38") (pinfunction "~{RST}_38") (pintype "passive"))
    )
    (net (code "71") (name "SW1") (class "Default")
      (node (ref "S2") (pin "2") (pinfunction "2_2") (pintype "passive"))
      (node (ref "U1") (pin "28") (pinfunction "PF0_28") (pintype "bidirectional"))
    )
    (net (code "72") (name "SW2") (class "Default")
      (node (ref "S3") (pin "2") (pinfunction "2_2") (pintype "passive"))
      (node (ref "U1") (pin "29") (pinfunction "PF1_29") (pintype "bidirectional"))
    )
    (net (code "73") (name "SW3") (class "Default")
      (node (ref "S4") (pin "2") (pinfunction "2_2") (pintype "passive"))
      (node (ref "U1") (pin "30") (pinfunction "PF2_30") (pintype "bidirectional"))
    )
    (net (code "74") (name "SW4") (class "Default")
      (node (ref "S5") (pin "2") (pinfunction "2_2") (pintype "passive"))
      (node (ref "U1") (pin "31") (pinfunction "PF3_31") (pintype "bidirectional"))
    )
    (net (code "75") (name "Speaker") (class "Default")
      (node (ref "R2") (pin "1") (pinfunction "1_1") (pintype "passive"))
      (node (ref "U1") (pin "21") (pinfunction "PA4/SSI0Rx_21") (pintype "bidirectional"))
    )
    (net (code "76") (name "VDDC") (class "Default")
      (node (ref "C6") (pin "1") (pinfunction "1_1") (pintype "passive"))
      (node (ref "C7") (pin "1") (pinfunction "1_1") (pintype "passive"))
      (node (ref "U1") (pin "25") (pinfunction "VDDC_25") (pintype "power_in"))
      (node (ref "U1") (pin "56") (pinfunction "VDDC_56") (pintype "power_in"))
    )
    (net (code "77") (name "VIN") (class "Default")
      (node (ref "C10") (pin "2") (pinfunction "2_2") (pintype "passive"))
      (node (ref "C21") (pin "2") (pinfunction "2_2") (pintype "passive"))
      (node (ref "C24") (pin "2") (pinfunction "2_2") (pintype "passive"))
      (node (ref "C8") (pin "1") (pinfunction "+_1") (pintype "passive"))
      (node (ref "HD13") (pin "1") (pinfunction "1_1") (pintype "passive"))
      (node (ref "HD13") (pin "2") (pinfunction "2_2") (pintype "passive"))
      (node (ref "IC3") (pin "3") (pinfunction "Vin_3") (pintype "passive"))
      (node (ref "IC4") (pin "3") (pinfunction "Vin_3") (pintype "passive"))
      (node (ref "IC5") (pin "3") (pinfunction "Vin_3") (pintype "passive"))
      (node (ref "L1") (pin "2") (pinfunction "2_2") (pintype "passive"))
    )
    (net (code "78") (name "XOSC0") (class "Default")
      (node (ref "C4") (pin "2") (pinfunction "2_2") (pintype "passive"))
      (node (ref "U1") (pin "34") (pinfunction "XOSC0_34") (pintype "passive"))
      (node (ref "X2") (pin "2") (pinfunction "2_2") (pintype "passive"))
    )
    (net (code "79") (name "XOSC1") (class "Default")
      (node (ref "C3") (pin "1") (pinfunction "1_1") (pintype "passive"))
      (node (ref "U1") (pin "36") (pinfunction "XOSC1_36") (pintype "passive"))
      (node (ref "X2") (pin "1") (pinfunction "1_1") (pintype "passive"))
    )
    (net (code "80") (name "unconnected-(HD3-Pad7)") (class "Default")
      (node (ref "HD3") (pin "7") (pinfunction "7_7") (pintype "passive+no_connect"))
    )
    (net (code "81") (name "unconnected-(HD7-Pad5)") (class "Default")
      (node (ref "HD7") (pin "5") (pinfunction "5_5") (pintype "passive+no_connect"))
    )
    (net (code "82") (name "unconnected-(HD7-Pad6)") (class "Default")
      (node (ref "HD7") (pin "6") (pinfunction "6_6") (pintype "passive+no_connect"))
    )
    (net (code "83") (name "unconnected-(HD7-Pad7)") (class "Default")
      (node (ref "HD7") (pin "7") (pinfunction "7_7") (pintype "passive+no_connect"))
    )
  )
)
